# IRSolarSensor.net
KiCad netlist of a schematic drawn in EAGLE
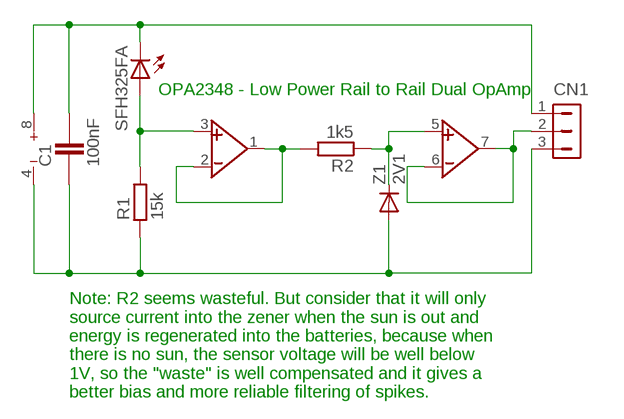
[diagram p0: schematic, sheet 1]

(export (version "E")
  (design (tool "Eeschema 10.0.6"))
  (components
    (comp (ref "C1")
      (value "100nF")
      (footprint "eagle-import:CAPC1608X92N")
      (libsource (lib "eagle-import") (part "CAPACITOR_0603"))
    )
    (comp (ref "CN1")
      (value "HDR-1X3-MTA-100")
      (footprint "eagle-import:MTA-100-3V")
      (libsource (lib "eagle-import") (part "HDR-1X3-MTA-100"))
    )
    (comp (ref "R1")
      (value "15k")
      (footprint "eagle-import:RESC2012X70N")
      (libsource (lib "eagle-import") (part "RESISTOR_0805"))
    )
    (comp (ref "R2")
      (value "1k5")
      (footprint "eagle-import:RESC1608X55N")
      (libsource (lib "eagle-import") (part "RESISTOR_0603"))
    )
    (comp (ref "SFH325FA")
      (value "LEDSIDELED")
      (footprint "eagle-import:OSRAM-SIDELED")
      (libsource (lib "eagle-import") (part "LEDSIDELED"))
    )
    (comp (ref "U$1")
      (value "OPA2348")
      (footprint "eagle-import:DCN-R-PDSO-G8")
      (libsource (lib "eagle-import") (part "OPA2348"))
    )
    (comp (ref "Z1")
      (value "2V1")
      (footprint "eagle-import:MINIMELF")
      (libsource (lib "eagle-import") (part "DIODE-MINIMELF"))
    )
  )
  (nets
    (net (code "1") (name "Net-(U$1A-V+)") (class "Default")
      (node (ref "C1") (pin "2") (pinfunction "2_2") (pintype "passive"))
      (node (ref "CN1") (pin "1") (pinfunction "1_1") (pintype "passive"))
      (node (ref "SFH325FA") (pin "C") (pinfunction "C_C") (pintype "passive"))
      (node (ref "U$1") (pin "8") (pinfunction "V+_8") (pintype "bidirectional"))
    )
    (net (code "2") (name "Net-(U$1A-V-)") (class "Default")
      (node (ref "C1") (pin "1") (pinfunction "1_1") (pintype "passive"))
      (node (ref "CN1") (pin "3") (pinfunction "3_3") (pintype "passive"))
      (node (ref "R1") (pin "1") (pinfunction "1_1") (pintype "passive"))
      (node (ref "U$1") (pin "4") (pinfunction "V-_4") (pintype "bidirectional"))
      (node (ref "Z1") (pin "A") (pinfunction "A_A") (pintype "passive"))
    )
    (net (code "3") (name "Net-(U$1B-+)") (class "Default")
      (node (ref "R2") (pin "1") (pinfunction "1_1") (pintype "passive"))
      (node (ref "U$1") (pin "5") (pinfunction "+_5") (pintype "bidirectional"))
      (node (ref "Z1") (pin "C") (pinfunction "C_C") (pintype "passive"))
    )
    (net (code "4") (name "Net-(U$1B--)") (class "Default")
      (node (ref "CN1") (pin "2") (pinfunction "2_2") (pintype "passive"))
      (node (ref "U$1") (pin "6") (pinfunction "-_6") (pintype "bidirectional"))
      (node (ref "U$1") (pin "7") (pinfunction "O_7") (pintype "output"))
    )
    (net (code "5") (name "Net-(U$1C-+)") (class "Default")
      (node (ref "R1") (pin "2") (pinfunction "2_2") (pintype "passive"))
      (node (ref "SFH325FA") (pin "A") (pinfunction "A_A") (pintype "passive"))
      (node (ref "U$1") (pin "3") (pinfunction "+_3") (pintype "bidirectional"))
    )
    (net (code "6") (name "Net-(U$1C--)") (class "Default")
      (node (ref "R2") (pin "2") (pinfunction "2_2") (pintype "passive"))
      (node (ref "U$1") (pin "1") (pinfunction "O_1") (pintype "output"))
      (node (ref "U$1") (pin "2") (pinfunction "-_2") (pintype "bidirectional"))
    )
  )
)
